# PFC_PWR_BOOST_CNV.net
KiCad netlist of a schematic drawn in Altium Designer
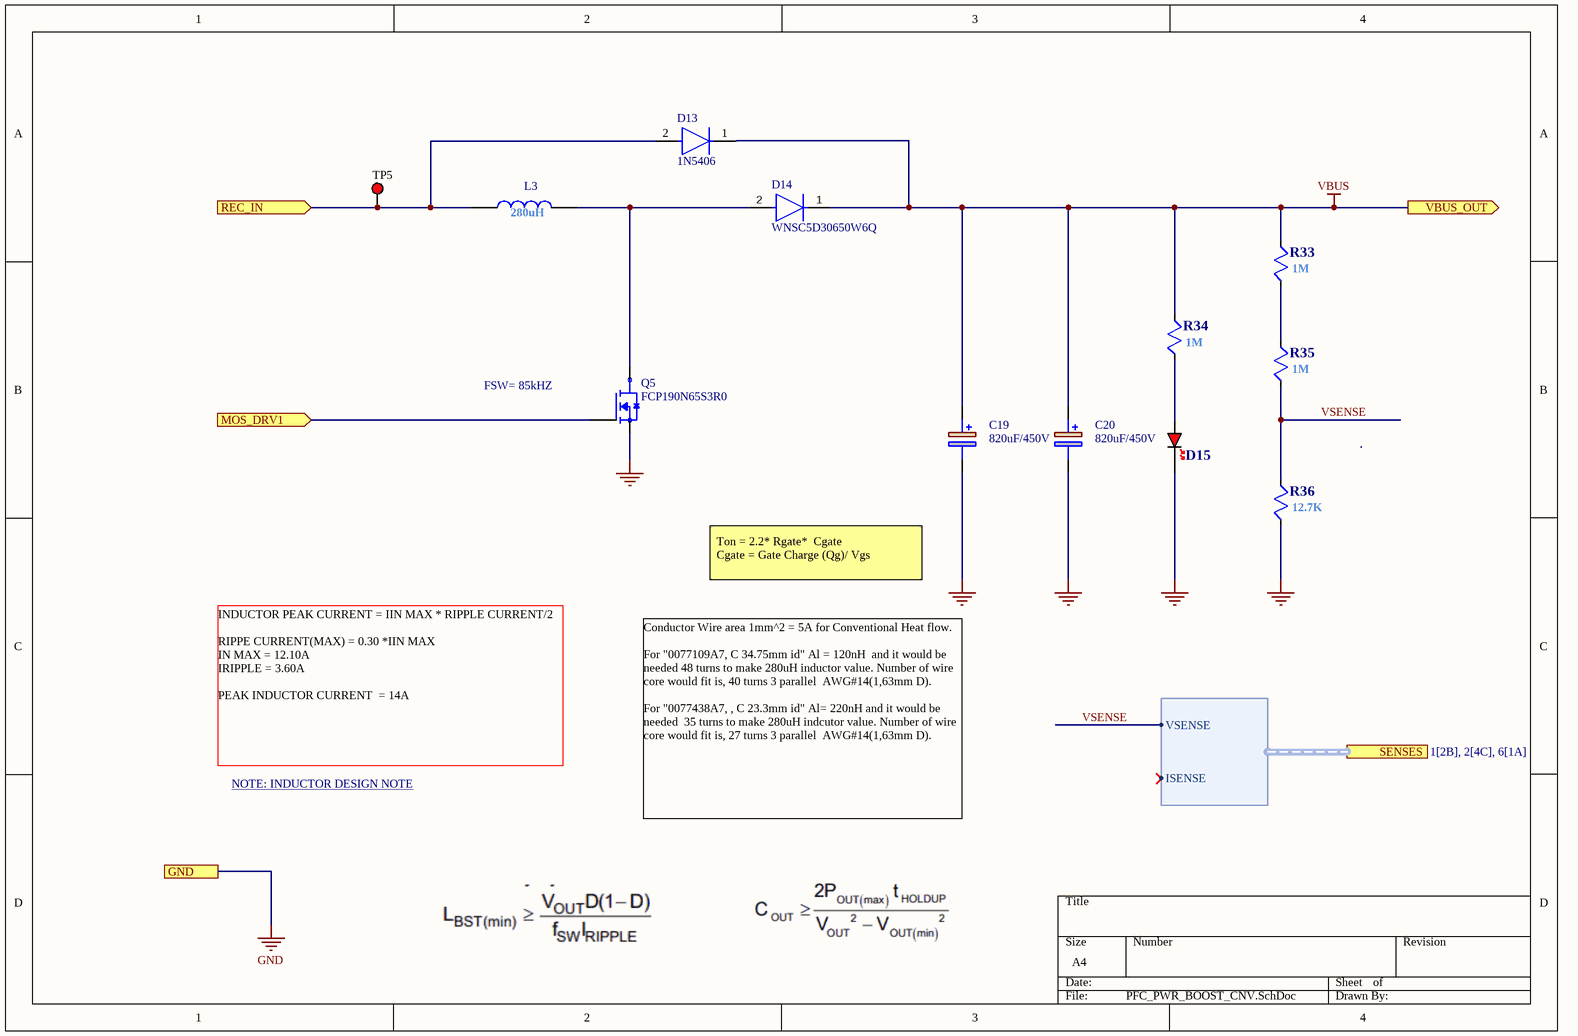
[diagram p0: PFC_PWR_BOOST_CNV.SchDoc]

(export (version "E")
  (design (tool "Eeschema 10.0.6"))
  (components
    (comp (ref "C19")
      (value "820uF/450V")
      (footprint "CAPPRD1000W180D3550H5250")
      (description "Aluminum Electrolytic Capacitors - Snap In 450V 820uF 20% Tol.")
      (fields
        (field (name "MOUSER PART NUMBER") "661-ESMR451N821MA50S")
        (field (name "MANUFACTURER_PART_NUMBER") "ESMR451VSN821MA50S")
      )
      (libsource (lib "Görev Yükü's Libary") (part "ESMR451VSN821MA50S"))
    )
    (comp (ref "C20")
      (value "820uF/450V")
      (footprint "CAPPRD1000W180D3550H5250")
      (description "Aluminum Electrolytic Capacitors - Snap In 450V 820uF 20% Tol.")
      (fields
        (field (name "MOUSER PART NUMBER") "661-ESMR451N821MA50S")
        (field (name "MANUFACTURER_PART_NUMBER") "ESMR451VSN821MA50S")
      )
      (libsource (lib "Görev Yükü's Libary") (part "ESMR451VSN821MA50S"))
    )
    (comp (ref "D13")
      (value "1N5406")
      (footprint "FP-1N5406-E3-54-MFG")
      (description "DIODE GEN PURP 600V 3A DO201AD")
      (libsource (lib "Altium Content Vault") (part "d7152d700b627762746794eb795d46e"))
    )
    (comp (ref "D14")
      (value "WNSC5D30650W6Q")
      (footprint "WNSC5D30650W6Q")
      (description "DIODE SIL.CARB.SCHOTTKY 30A 650V TO247F-2L THT")
      (libsource (lib "Görev Yükü's Libary") (part "WNSC5D30650W6Q"))
    )
    (comp (ref "D15")
      (value "19-21/R6C-AP1Q2/4T")
      (footprint "LED_0603_RED")
      (description "LED SMD 0603 RED 28.5-72mcd 100° WATER CLEAR")
      (libsource (lib "Phil-lab") (part "LED_0603_RED"))
    )
    (comp (ref "L3")
      (value "280uH")
      (footprint "0077438A7")
      (fields (field (name "Comment") "0077438A7"))
      (libsource (lib "Görev Yükü's Libary") (part "0077438A7"))
    )
    (comp (ref "Q5")
      (value "FCP190N65S3R0")
      (footprint "Mosfet_T0220")
      (description "MOSFET DIS.17A 650V N-CH TO220-3")
      (libsource (lib "Görev Yükü's Libary") (part "Mosfet_TO220"))
    )
    (comp (ref "R33")
      (value "1M")
      (footprint "PCB_EZ_BuckPowerDriver V2.0:RESC1608N")
      (description "RES.(1608) 0603 1M Ohms 5% 1/10W-S 100PPM")
      (fields (field (name "Comment") "0603SAJ0105TDE"))
      (libsource (lib "WG_MainBoard_NV1") (part "RES"))
    )
    (comp (ref "R34")
      (value "1M")
      (footprint "PCB_EZ_BuckPowerDriver V2.0:RESC1608N")
      (description "RES.(1608) 0603 1M Ohms 5% 1/10W-S 100PPM")
      (fields (field (name "Comment") "0603SAJ0105TDE"))
      (libsource (lib "WG_MainBoard_NV1") (part "RES"))
    )
    (comp (ref "R35")
      (value "1M")
      (footprint "PCB_EZ_BuckPowerDriver V2.0:RESC1608N")
      (description "RES.(1608) 0603 1M Ohms 5% 1/10W-S 100PPM")
      (fields (field (name "Comment") "0603SAJ0105TDE"))
      (libsource (lib "WG_MainBoard_NV1") (part "RES"))
    )
    (comp (ref "R36")
      (value "12.7K")
      (footprint "PCB_EZ_BuckPowerDriver V3.0:RESC1608N")
      (description "RES.(1608) 0603 12.7K Ohms 1% 1/4W 100PPM")
      (fields (field (name "Comment") "CR-03FA7--12K7"))
      (libsource (lib "WG_MainBoard_NV1") (part "RES"))
    )
    (comp (ref "TP5")
      (value "5010")
      (footprint "KSTN-5010_V")
      (description "Test Point, Red, Through Hole, RoHS, Bulk")
      (fields (field (name "MANUFACTURER") "Keystone"))
      (libsource (lib "Altium Content Vault") (part "TESTPOINT_RED"))
    )
  )
  (nets
    (net (code "2") (name "/MOS_DRV1") (class "Default")
      (node (ref "Q5") (pin "1") (pinfunction "G_1") (pintype "passive"))
    )
    (net (code "3") (name "/REC_IN") (class "Default")
      (node (ref "D13") (pin "2") (pinfunction "A_2") (pintype "passive"))
      (node (ref "L3") (pin "1") (pinfunction "1_1") (pintype "passive"))
      (node (ref "TP5") (pin "1") (pinfunction "1_1") (pintype "passive"))
    )
    (net (code "4") (name "/VSENSE") (class "Default")
      (node (ref "R35") (pin "2") (pinfunction "2_2") (pintype "passive"))
      (node (ref "R36") (pin "1") (pinfunction "1_1") (pintype "passive"))
    )
    (net (code "6") (name "GND") (class "Default")
      (node (ref "C19") (pin "2") (pinfunction "-_2") (pintype "passive"))
      (node (ref "C20") (pin "2") (pinfunction "-_2") (pintype "passive"))
      (node (ref "D15") (pin "K") (pinfunction "K_K") (pintype "passive"))
      (node (ref "Q5") (pin "3") (pinfunction "S_3") (pintype "passive"))
      (node (ref "R36") (pin "2") (pinfunction "2_2") (pintype "passive"))
    )
    (net (code "7") (name "Net-(D14-A)") (class "Default")
      (node (ref "D14") (pin "2") (pinfunction "A_2") (pintype "passive"))
      (node (ref "L3") (pin "2") (pinfunction "2_2") (pintype "passive"))
      (node (ref "Q5") (pin "2") (pinfunction "D_2") (pintype "passive"))
    )
    (net (code "8") (name "Net-(D15-PadA)") (class "Default")
      (node (ref "D15") (pin "A") (pinfunction "A_A") (pintype "passive"))
      (node (ref "R34") (pin "2") (pinfunction "2_2") (pintype "passive"))
    )
    (net (code "9") (name "Net-(R33-Pad2)") (class "Default")
      (node (ref "R33") (pin "2") (pinfunction "2_2") (pintype "passive"))
      (node (ref "R35") (pin "1") (pinfunction "1_1") (pintype "passive"))
    )
    (net (code "10") (name "VBUS") (class "Default")
      (node (ref "C19") (pin "1") (pinfunction "+_1") (pintype "passive"))
      (node (ref "C20") (pin "1") (pinfunction "+_1") (pintype "passive"))
      (node (ref "D13") (pin "1") (pinfunction "C_1") (pintype "passive"))
      (node (ref "D14") (pin "1") (pinfunction "K_1") (pintype "passive"))
      (node (ref "R33") (pin "1") (pinfunction "1_1") (pintype "passive"))
      (node (ref "R34") (pin "1") (pinfunction "1_1") (pintype "passive"))
    )
  )
)
